# Transceivers_Ver2.net
KiCad netlist of a schematic drawn in EAGLE
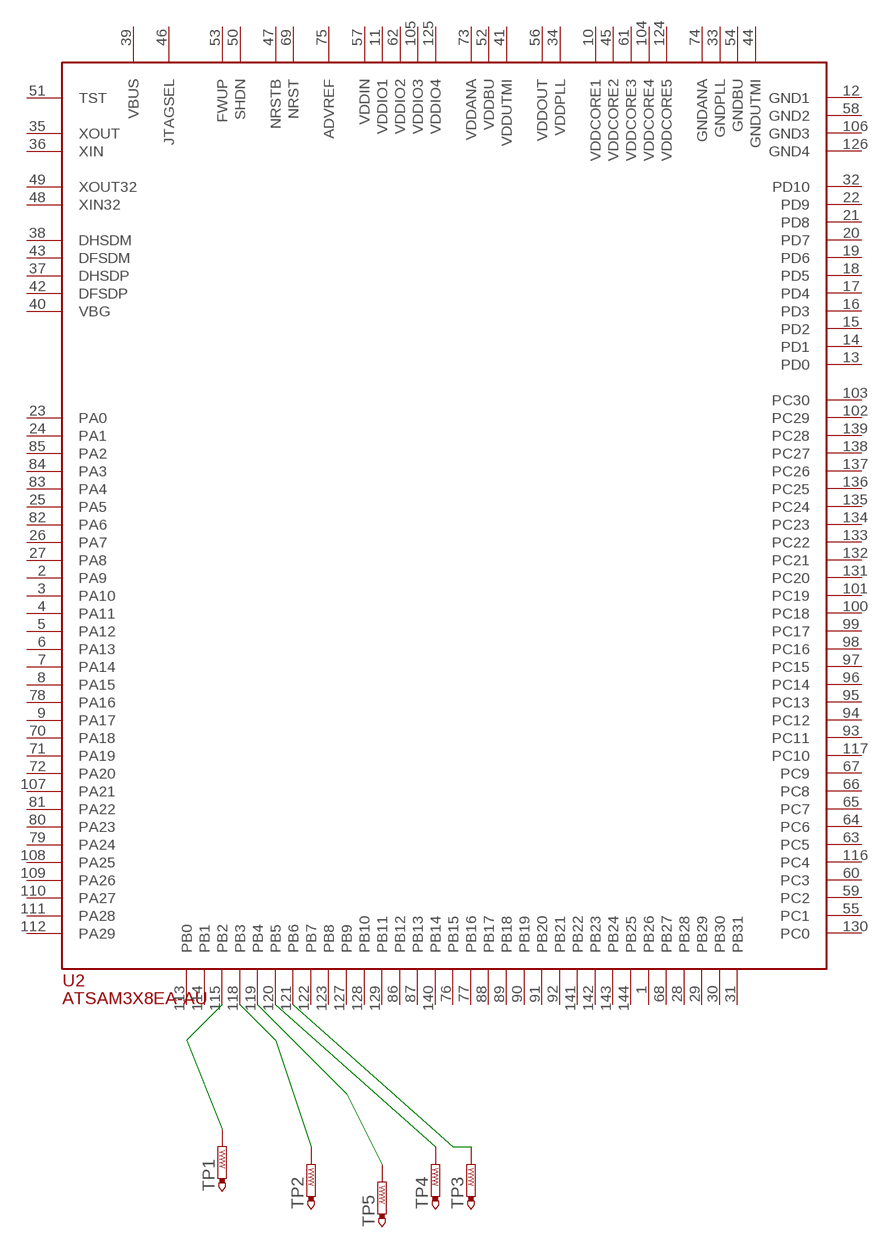
[diagram p0: schematic, sheet 1, part 1 of 2]
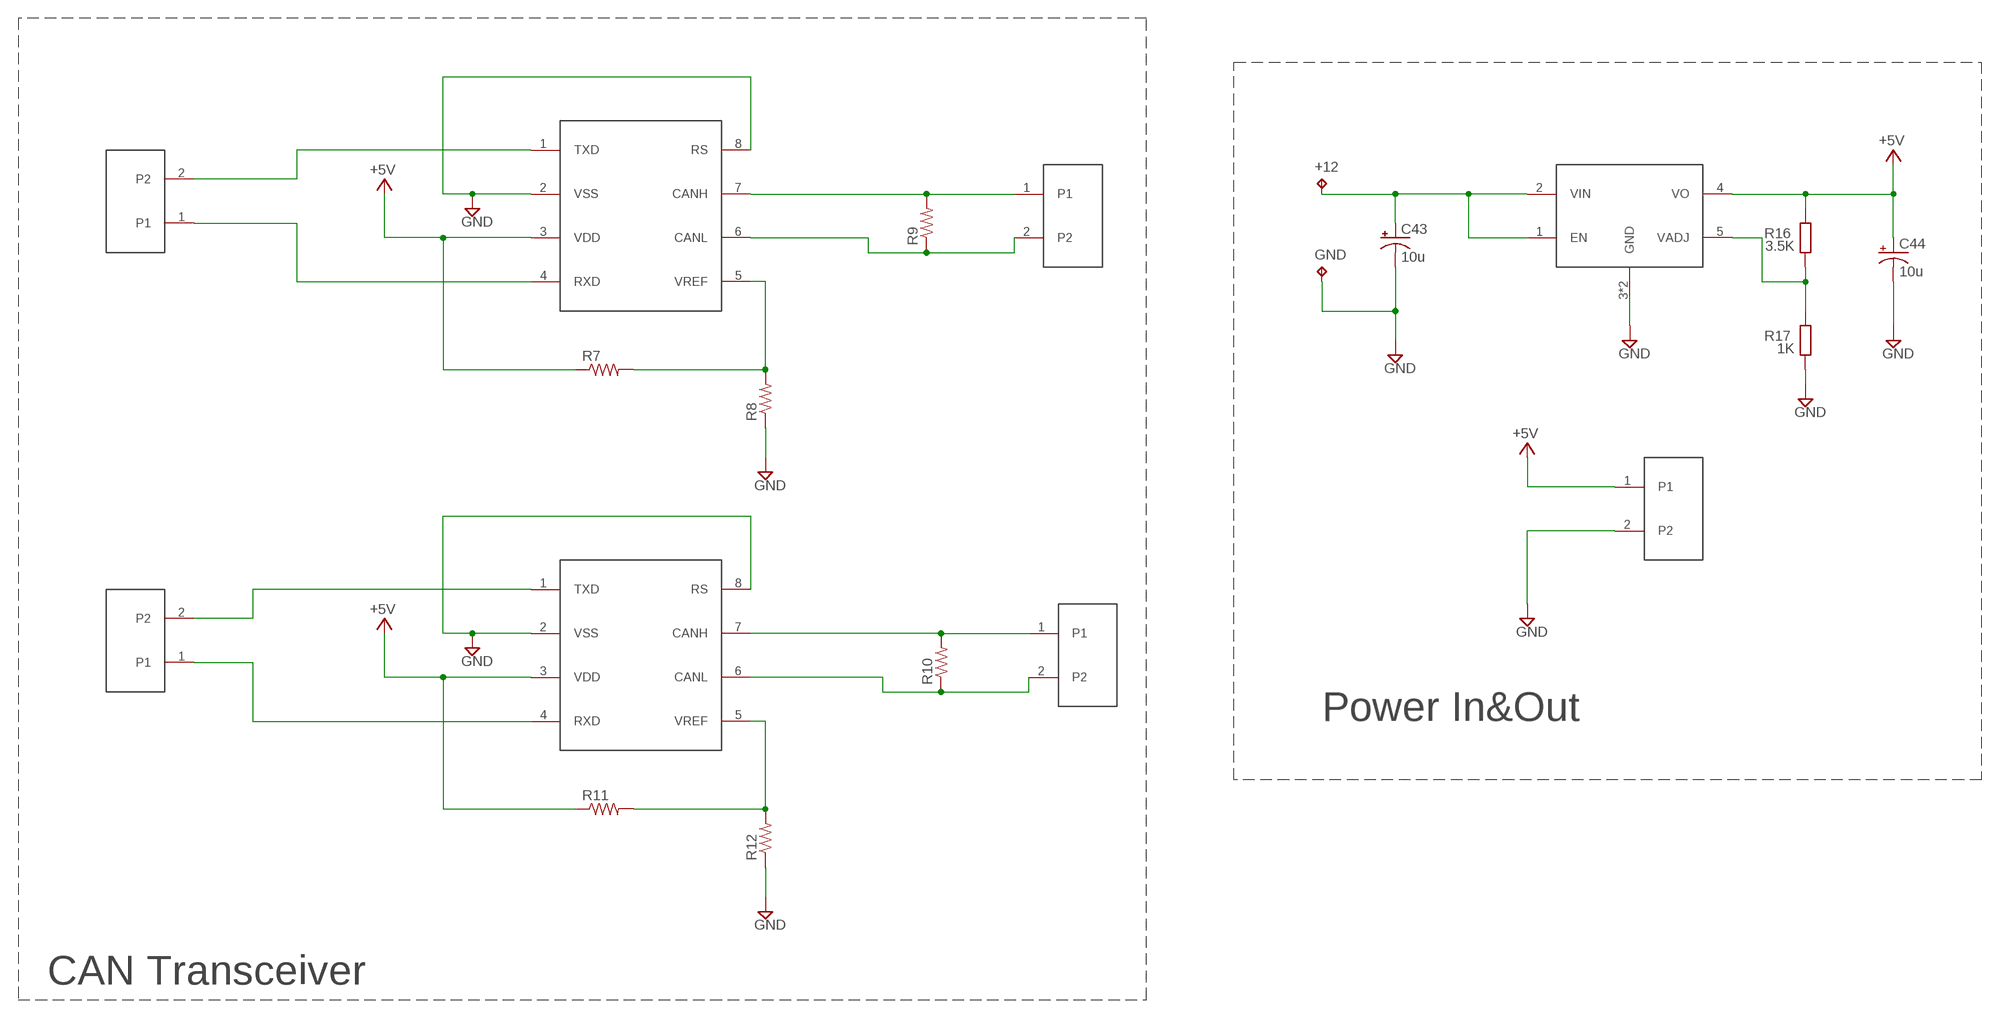
[diagram p1: schematic, sheet 1, part 2 of 2]

(export (version "E")
  (design (tool "Eeschema 10.0.6"))
  (components
    (comp (ref "+12")
      (value "TPPAD1-13")
      (footprint "eagle-import:P1-13")
      (libsource (lib "eagle-import") (part "TPPAD1-13"))
    )
    (comp (ref "C43")
      (value "10u")
      (footprint "eagle-import:153CLV-0405")
      (libsource (lib "eagle-import") (part "CPOL-US153CLV-0405"))
    )
    (comp (ref "C44")
      (value "10u")
      (footprint "eagle-import:153CLV-0405")
      (libsource (lib "eagle-import") (part "CPOL-US153CLV-0405"))
    )
    (comp (ref "CAN0")
      (value "CON-100MIL")
      (footprint "eagle-import:2X1-100MIL")
      (libsource (lib "eagle-import") (part "CON-100MIL"))
    )
    (comp (ref "CAN1")
      (value "CON-100MIL")
      (footprint "eagle-import:2X1-100MIL")
      (libsource (lib "eagle-import") (part "CON-100MIL"))
    )
    (comp (ref "GND")
      (value "TPPAD1-13")
      (footprint "eagle-import:P1-13")
      (libsource (lib "eagle-import") (part "TPPAD1-13"))
    )
    (comp (ref "POWER")
      (value "CON-100MIL")
      (footprint "eagle-import:2X1-100MIL")
      (libsource (lib "eagle-import") (part "CON-100MIL"))
    )
    (comp (ref "R7")
      (value "R-US_R0805")
      (footprint "eagle-import:R0805")
      (libsource (lib "eagle-import") (part "R-US_R0805"))
    )
    (comp (ref "R8")
      (value "R-US_R0805")
      (footprint "eagle-import:R0805")
      (libsource (lib "eagle-import") (part "R-US_R0805"))
    )
    (comp (ref "R9")
      (value "R-US_R0805")
      (footprint "eagle-import:R0805")
      (libsource (lib "eagle-import") (part "R-US_R0805"))
    )
    (comp (ref "R10")
      (value "R-US_R0805")
      (footprint "eagle-import:R0805")
      (libsource (lib "eagle-import") (part "R-US_R0805"))
    )
    (comp (ref "R11")
      (value "R-US_R0805")
      (footprint "eagle-import:R0805")
      (libsource (lib "eagle-import") (part "R-US_R0805"))
    )
    (comp (ref "R12")
      (value "R-US_R0805")
      (footprint "eagle-import:R0805")
      (libsource (lib "eagle-import") (part "R-US_R0805"))
    )
    (comp (ref "R16")
      (value "3.5K")
      (footprint "eagle-import:R0805")
      (libsource (lib "eagle-import") (part "R-EU_R0805"))
    )
    (comp (ref "R17")
      (value "1K")
      (footprint "eagle-import:R0805")
      (libsource (lib "eagle-import") (part "R-EU_R0805"))
    )
    (comp (ref "TP1")
      (value "PTR1PAD1-13Y")
      (footprint "eagle-import:P1-13Y")
      (libsource (lib "eagle-import") (part "PTR1PAD1-13Y"))
    )
    (comp (ref "TP2")
      (value "PTR1PAD1-13Y")
      (footprint "eagle-import:P1-13Y")
      (libsource (lib "eagle-import") (part "PTR1PAD1-13Y"))
    )
    (comp (ref "TP3")
      (value "PTR1PAD1-13Y")
      (footprint "eagle-import:P1-13Y")
      (libsource (lib "eagle-import") (part "PTR1PAD1-13Y"))
    )
    (comp (ref "TP4")
      (value "PTR1PAD1-13Y")
      (footprint "eagle-import:P1-13Y")
      (libsource (lib "eagle-import") (part "PTR1PAD1-13Y"))
    )
    (comp (ref "TP5")
      (value "PTR1PAD1-13Y")
      (footprint "eagle-import:P1-13Y")
      (libsource (lib "eagle-import") (part "PTR1PAD1-13Y"))
    )
    (comp (ref "TXRX0")
      (value "CON-100MIL")
      (footprint "eagle-import:2X1-100MIL")
      (libsource (lib "eagle-import") (part "CON-100MIL"))
    )
    (comp (ref "TXRX1")
      (value "CON-100MIL")
      (footprint "eagle-import:2X1-100MIL")
      (libsource (lib "eagle-import") (part "CON-100MIL"))
    )
    (comp (ref "U1")
      (value "MCP2551")
      (footprint "eagle-import:SOIC8")
      (libsource (lib "eagle-import") (part "MCP2551"))
    )
    (comp (ref "U2")
      (value "ATSAM3X8EA-AU")
      (footprint "eagle-import:LQFP144")
      (libsource (lib "eagle-import") (part "ATSAM3X/AAU"))
    )
    (comp (ref "U4")
      (value "MCP2551")
      (footprint "eagle-import:SOIC8")
      (libsource (lib "eagle-import") (part "MCP2551"))
    )
    (comp (ref "U5")
      (value "TLF1963TBATMA1")
      (footprint "eagle-import:DPAK")
      (libsource (lib "eagle-import") (part "TLF1963"))
    )
  )
  (nets
    (net (code "1") (name "+5V") (class "Default")
      (node (ref "C44") (pin "+") (pinfunction "+_+") (pintype "passive"))
      (node (ref "POWER") (pin "1") (pinfunction "P1_1") (pintype "bidirectional"))
      (node (ref "R11") (pin "1") (pinfunction "1_1") (pintype "passive"))
      (node (ref "R16") (pin "2") (pinfunction "2_2") (pintype "passive"))
      (node (ref "R7") (pin "1") (pinfunction "1_1") (pintype "passive"))
      (node (ref "U1") (pin "3") (pinfunction "VDD_3") (pintype "bidirectional"))
      (node (ref "U4") (pin "3") (pinfunction "VDD_3") (pintype "bidirectional"))
      (node (ref "U5") (pin "4") (pinfunction "VO_4") (pintype "bidirectional"))
    )
    (net (code "2") (name "/ADVREF") (class "Default")
      (node (ref "U2") (pin "75") (pinfunction "ADVREF_75") (pintype "power_in"))
    )
    (net (code "3") (name "/GND1") (class "Default")
      (node (ref "U2") (pin "12") (pinfunction "GND1_12") (pintype "power_in"))
    )
    (net (code "4") (name "/GND2") (class "Default")
      (node (ref "U2") (pin "58") (pinfunction "GND2_58") (pintype "power_in"))
    )
    (net (code "5") (name "/GND3") (class "Default")
      (node (ref "U2") (pin "106") (pinfunction "GND3_106") (pintype "power_in"))
    )
    (net (code "6") (name "/GND4") (class "Default")
      (node (ref "U2") (pin "126") (pinfunction "GND4_126") (pintype "power_in"))
    )
    (net (code "7") (name "/GNDANA") (class "Default")
      (node (ref "U2") (pin "74") (pinfunction "GNDANA_74") (pintype "power_in"))
    )
    (net (code "8") (name "/GNDBU") (class "Default")
      (node (ref "U2") (pin "54") (pinfunction "GNDBU_54") (pintype "power_in"))
    )
    (net (code "9") (name "/GNDPLL") (class "Default")
      (node (ref "U2") (pin "33") (pinfunction "GNDPLL_33") (pintype "power_in"))
    )
    (net (code "10") (name "/GNDUTMI") (class "Default")
      (node (ref "U2") (pin "44") (pinfunction "GNDUTMI_44") (pintype "power_in"))
    )
    (net (code "11") (name "/VBUS") (class "Default")
      (node (ref "U2") (pin "39") (pinfunction "VBUS_39") (pintype "power_in"))
    )
    (net (code "12") (name "/VDDANA") (class "Default")
      (node (ref "U2") (pin "73") (pinfunction "VDDANA_73") (pintype "power_in"))
    )
    (net (code "13") (name "/VDDBU") (class "Default")
      (node (ref "U2") (pin "52") (pinfunction "VDDBU_52") (pintype "power_in"))
    )
    (net (code "14") (name "/VDDIN") (class "Default")
      (node (ref "U2") (pin "57") (pinfunction "VDDIN_57") (pintype "power_in"))
    )
    (net (code "15") (name "/VDDIO1") (class "Default")
      (node (ref "U2") (pin "11") (pinfunction "VDDIO1_11") (pintype "power_in"))
    )
    (net (code "16") (name "/VDDIO2") (class "Default")
      (node (ref "U2") (pin "62") (pinfunction "VDDIO2_62") (pintype "power_in"))
    )
    (net (code "17") (name "/VDDIO3") (class "Default")
      (node (ref "U2") (pin "105") (pinfunction "VDDIO3_105") (pintype "power_in"))
    )
    (net (code "18") (name "/VDDIO4") (class "Default")
      (node (ref "U2") (pin "125") (pinfunction "VDDIO4_125") (pintype "power_in"))
    )
    (net (code "19") (name "GND") (class "Default")
      (node (ref "C43") (pin "-") (pinfunction "-_-") (pintype "passive"))
      (node (ref "C44") (pin "-") (pinfunction "-_-") (pintype "passive"))
      (node (ref "GND") (pin "TP") (pinfunction "TP_TP") (pintype "input"))
      (node (ref "POWER") (pin "2") (pinfunction "P2_2") (pintype "bidirectional"))
      (node (ref "R12") (pin "1") (pinfunction "1_1") (pintype "passive"))
      (node (ref "R17") (pin "1") (pinfunction "1_1") (pintype "passive"))
      (node (ref "R8") (pin "1") (pinfunction "1_1") (pintype "passive"))
      (node (ref "U1") (pin "2") (pinfunction "VSS_2") (pintype "bidirectional"))
      (node (ref "U1") (pin "8") (pinfunction "RS_8") (pintype "bidirectional"))
      (node (ref "U4") (pin "2") (pinfunction "VSS_2") (pintype "bidirectional"))
      (node (ref "U4") (pin "8") (pinfunction "RS_8") (pintype "bidirectional"))
      (node (ref "U5") (pin "3") (pinfunction "GND_3") (pintype "bidirectional"))
      (node (ref "U5") (pin "6") (pinfunction "GND_6") (pintype "bidirectional"))
    )
    (net (code "20") (name "Net-(CAN0-P1)") (class "Default")
      (node (ref "CAN0") (pin "1") (pinfunction "P1_1") (pintype "bidirectional"))
      (node (ref "R9") (pin "2") (pinfunction "2_2") (pintype "passive"))
      (node (ref "U1") (pin "7") (pinfunction "CANH_7") (pintype "bidirectional"))
    )
    (net (code "21") (name "Net-(CAN0-P2)") (class "Default")
      (node (ref "CAN0") (pin "2") (pinfunction "P2_2") (pintype "bidirectional"))
      (node (ref "R9") (pin "1") (pinfunction "1_1") (pintype "passive"))
      (node (ref "U1") (pin "6") (pinfunction "CANL_6") (pintype "bidirectional"))
    )
    (net (code "22") (name "Net-(CAN1-P1)") (class "Default")
      (node (ref "CAN1") (pin "1") (pinfunction "P1_1") (pintype "bidirectional"))
      (node (ref "R10") (pin "2") (pinfunction "2_2") (pintype "passive"))
      (node (ref "U4") (pin "7") (pinfunction "CANH_7") (pintype "bidirectional"))
    )
    (net (code "23") (name "Net-(CAN1-P2)") (class "Default")
      (node (ref "CAN1") (pin "2") (pinfunction "P2_2") (pintype "bidirectional"))
      (node (ref "R10") (pin "1") (pinfunction "1_1") (pintype "passive"))
      (node (ref "U4") (pin "6") (pinfunction "CANL_6") (pintype "bidirectional"))
    )
    (net (code "24") (name "Net-(TXRX0-P1)") (class "Default")
      (node (ref "TXRX0") (pin "1") (pinfunction "P1_1") (pintype "bidirectional"))
      (node (ref "U1") (pin "4") (pinfunction "RXD_4") (pintype "bidirectional"))
    )
    (net (code "25") (name "Net-(TXRX0-P2)") (class "Default")
      (node (ref "TXRX0") (pin "2") (pinfunction "P2_2") (pintype "bidirectional"))
      (node (ref "U1") (pin "1") (pinfunction "TXD_1") (pintype "bidirectional"))
    )
    (net (code "26") (name "Net-(TXRX1-P1)") (class "Default")
      (node (ref "TXRX1") (pin "1") (pinfunction "P1_1") (pintype "bidirectional"))
      (node (ref "U4") (pin "4") (pinfunction "RXD_4") (pintype "bidirectional"))
    )
    (net (code "27") (name "Net-(TXRX1-P2)") (class "Default")
      (node (ref "TXRX1") (pin "2") (pinfunction "P2_2") (pintype "bidirectional"))
      (node (ref "U4") (pin "1") (pinfunction "TXD_1") (pintype "bidirectional"))
    )
    (net (code "28") (name "Net-(U1-VREF)") (class "Default")
      (node (ref "R7") (pin "2") (pinfunction "2_2") (pintype "passive"))
      (node (ref "R8") (pin "2") (pinfunction "2_2") (pintype "passive"))
      (node (ref "U1") (pin "5") (pinfunction "VREF_5") (pintype "bidirectional"))
    )
    (net (code "29") (name "Net-(U2-PB2)") (class "Default")
      (node (ref "TP1") (pin "TP") (pinfunction "TP_TP") (pintype "input"))
      (node (ref "U2") (pin "115") (pinfunction "PB2_115") (pintype "bidirectional"))
    )
    (net (code "30") (name "Net-(U2-PB3)") (class "Default")
      (node (ref "TP2") (pin "TP") (pinfunction "TP_TP") (pintype "input"))
      (node (ref "U2") (pin "118") (pinfunction "PB3_118") (pintype "bidirectional"))
    )
    (net (code "31") (name "Net-(U2-PB4)") (class "Default")
      (node (ref "TP5") (pin "TP") (pinfunction "TP_TP") (pintype "input"))
      (node (ref "U2") (pin "119") (pinfunction "PB4_119") (pintype "bidirectional"))
    )
    (net (code "32") (name "Net-(U2-PB5)") (class "Default")
      (node (ref "TP4") (pin "TP") (pinfunction "TP_TP") (pintype "input"))
      (node (ref "U2") (pin "120") (pinfunction "PB5_120") (pintype "bidirectional"))
    )
    (net (code "33") (name "Net-(U2-PB6)") (class "Default")
      (node (ref "TP3") (pin "TP") (pinfunction "TP_TP") (pintype "input"))
      (node (ref "U2") (pin "121") (pinfunction "PB6_121") (pintype "bidirectional"))
    )
    (net (code "34") (name "Net-(U4-VREF)") (class "Default")
      (node (ref "R11") (pin "2") (pinfunction "2_2") (pintype "passive"))
      (node (ref "R12") (pin "2") (pinfunction "2_2") (pintype "passive"))
      (node (ref "U4") (pin "5") (pinfunction "VREF_5") (pintype "bidirectional"))
    )
    (net (code "35") (name "Net-(U5-EN)") (class "Default")
      (node (ref "+12") (pin "TP") (pinfunction "TP_TP") (pintype "input"))
      (node (ref "C43") (pin "+") (pinfunction "+_+") (pintype "passive"))
      (node (ref "U5") (pin "1") (pinfunction "EN_1") (pintype "bidirectional"))
      (node (ref "U5") (pin "2") (pinfunction "VIN_2") (pintype "bidirectional"))
    )
    (net (code "36") (name "Net-(U5-VADJ)") (class "Default")
      (node (ref "R16") (pin "1") (pinfunction "1_1") (pintype "passive"))
      (node (ref "R17") (pin "2") (pinfunction "2_2") (pintype "passive"))
      (node (ref "U5") (pin "5") (pinfunction "VADJ_5") (pintype "bidirectional"))
    )
    (net (code "37") (name "unconnected-(U2-DFSDM-Pad43)") (class "Default")
      (node (ref "U2") (pin "43") (pinfunction "DFSDM_43") (pintype "input"))
    )
    (net (code "38") (name "unconnected-(U2-DFSDP-Pad42)") (class "Default")
      (node (ref "U2") (pin "42") (pinfunction "DFSDP_42") (pintype "input"))
    )
    (net (code "39") (name "unconnected-(U2-DHSDM-Pad38)") (class "Default")
      (node (ref "U2") (pin "38") (pinfunction "DHSDM_38") (pintype "bidirectional"))
    )
    (net (code "40") (name "unconnected-(U2-DHSDP-Pad37)") (class "Default")
      (node (ref "U2") (pin "37") (pinfunction "DHSDP_37") (pintype "bidirectional"))
    )
    (net (code "41") (name "unconnected-(U2-FWUP-Pad53)") (class "Default")
      (node (ref "U2") (pin "53") (pinfunction "FWUP_53") (pintype "input"))
    )
    (net (code "42") (name "unconnected-(U2-JTAGSEL-Pad46)") (class "Default")
      (node (ref "U2") (pin "46") (pinfunction "JTAGSEL_46") (pintype "input"))
    )
    (net (code "43") (name "unconnected-(U2-NRST-Pad69)") (class "Default")
      (node (ref "U2") (pin "69") (pinfunction "NRST_69") (pintype "bidirectional"))
    )
    (net (code "44") (name "unconnected-(U2-NRSTB-Pad47)") (class "Default")
      (node (ref "U2") (pin "47") (pinfunction "NRSTB_47") (pintype "input"))
    )
    (net (code "45") (name "unconnected-(U2-PA0-Pad23)") (class "Default")
      (node (ref "U2") (pin "23") (pinfunction "PA0_23") (pintype "bidirectional"))
    )
    (net (code "46") (name "unconnected-(U2-PA1-Pad24)") (class "Default")
      (node (ref "U2") (pin "24") (pinfunction "PA1_24") (pintype "bidirectional"))
    )
    (net (code "47") (name "unconnected-(U2-PA2-Pad85)") (class "Default")
      (node (ref "U2") (pin "85") (pinfunction "PA2_85") (pintype "bidirectional"))
    )
    (net (code "48") (name "unconnected-(U2-PA3-Pad84)") (class "Default")
      (node (ref "U2") (pin "84") (pinfunction "PA3_84") (pintype "bidirectional"))
    )
    (net (code "49") (name "unconnected-(U2-PA4-Pad83)") (class "Default")
      (node (ref "U2") (pin "83") (pinfunction "PA4_83") (pintype "bidirectional"))
    )
    (net (code "50") (name "unconnected-(U2-PA5-Pad25)") (class "Default")
      (node (ref "U2") (pin "25") (pinfunction "PA5_25") (pintype "bidirectional"))
    )
    (net (code "51") (name "unconnected-(U2-PA6-Pad82)") (class "Default")
      (node (ref "U2") (pin "82") (pinfunction "PA6_82") (pintype "bidirectional"))
    )
    (net (code "52") (name "unconnected-(U2-PA7-Pad26)") (class "Default")
      (node (ref "U2") (pin "26") (pinfunction "PA7_26") (pintype "bidirectional"))
    )
    (net (code "53") (name "unconnected-(U2-PA8-Pad27)") (class "Default")
      (node (ref "U2") (pin "27") (pinfunction "PA8_27") (pintype "bidirectional"))
    )
    (net (code "54") (name "unconnected-(U2-PA9-Pad2)") (class "Default")
      (node (ref "U2") (pin "2") (pinfunction "PA9_2") (pintype "bidirectional"))
    )
    (net (code "55") (name "unconnected-(U2-PA10-Pad3)") (class "Default")
      (node (ref "U2") (pin "3") (pinfunction "PA10_3") (pintype "bidirectional"))
    )
    (net (code "56") (name "unconnected-(U2-PA11-Pad4)") (class "Default")
      (node (ref "U2") (pin "4") (pinfunction "PA11_4") (pintype "bidirectional"))
    )
    (net (code "57") (name "unconnected-(U2-PA12-Pad5)") (class "Default")
      (node (ref "U2") (pin "5") (pinfunction "PA12_5") (pintype "bidirectional"))
    )
    (net (code "58") (name "unconnected-(U2-PA13-Pad6)") (class "Default")
      (node (ref "U2") (pin "6") (pinfunction "PA13_6") (pintype "bidirectional"))
    )
    (net (code "59") (name "unconnected-(U2-PA14-Pad7)") (class "Default")
      (node (ref "U2") (pin "7") (pinfunction "PA14_7") (pintype "bidirectional"))
    )
    (net (code "60") (name "unconnected-(U2-PA15-Pad8)") (class "Default")
      (node (ref "U2") (pin "8") (pinfunction "PA15_8") (pintype "bidirectional"))
    )
    (net (code "61") (name "unconnected-(U2-PA16-Pad78)") (class "Default")
      (node (ref "U2") (pin "78") (pinfunction "PA16_78") (pintype "bidirectional"))
    )
    (net (code "62") (name "unconnected-(U2-PA17-Pad9)") (class "Default")
      (node (ref "U2") (pin "9") (pinfunction "PA17_9") (pintype "bidirectional"))
    )
    (net (code "63") (name "unconnected-(U2-PA18-Pad70)") (class "Default")
      (node (ref "U2") (pin "70") (pinfunction "PA18_70") (pintype "bidirectional"))
    )
    (net (code "64") (name "unconnected-(U2-PA19-Pad71)") (class "Default")
      (node (ref "U2") (pin "71") (pinfunction "PA19_71") (pintype "bidirectional"))
    )
    (net (code "65") (name "unconnected-(U2-PA20-Pad72)") (class "Default")
      (node (ref "U2") (pin "72") (pinfunction "PA20_72") (pintype "bidirectional"))
    )
    (net (code "66") (name "unconnected-(U2-PA21-Pad107)") (class "Default")
      (node (ref "U2") (pin "107") (pinfunction "PA21_107") (pintype "bidirectional"))
    )
    (net (code "67") (name "unconnected-(U2-PA22-Pad81)") (class "Default")
      (node (ref "U2") (pin "81") (pinfunction "PA22_81") (pintype "bidirectional"))
    )
    (net (code "68") (name "unconnected-(U2-PA23-Pad80)") (class "Default")
      (node (ref "U2") (pin "80") (pinfunction "PA23_80") (pintype "bidirectional"))
    )
    (net (code "69") (name "unconnected-(U2-PA24-Pad79)") (class "Default")
      (node (ref "U2") (pin "79") (pinfunction "PA24_79") (pintype "bidirectional"))
    )
    (net (code "70") (name "unconnected-(U2-PA25-Pad108)") (class "Default")
      (node (ref "U2") (pin "108") (pinfunction "PA25_108") (pintype "bidirectional"))
    )
    (net (code "71") (name "unconnected-(U2-PA26-Pad109)") (class "Default")
      (node (ref "U2") (pin "109") (pinfunction "PA26_109") (pintype "bidirectional"))
    )
    (net (code "72") (name "unconnected-(U2-PA27-Pad110)") (class "Default")
      (node (ref "U2") (pin "110") (pinfunction "PA27_110") (pintype "bidirectional"))
    )
    (net (code "73") (name "unconnected-(U2-PA28-Pad111)") (class "Default")
      (node (ref "U2") (pin "111") (pinfunction "PA28_111") (pintype "bidirectional"))
    )
    (net (code "74") (name "unconnected-(U2-PA29-Pad112)") (class "Default")
      (node (ref "U2") (pin "112") (pinfunction "PA29_112") (pintype "bidirectional"))
    )
    (net (code "75") (name "unconnected-(U2-PB0-Pad113)") (class "Default")
      (node (ref "U2") (pin "113") (pinfunction "PB0_113") (pintype "bidirectional"))
    )
    (net (code "76") (name "unconnected-(U2-PB1-Pad114)") (class "Default")
      (node (ref "U2") (pin "114") (pinfunction "PB1_114") (pintype "bidirectional"))
    )
    (net (code "77") (name "unconnected-(U2-PB7-Pad122)") (class "Default")
      (node (ref "U2") (pin "122") (pinfunction "PB7_122") (pintype "bidirectional"))
    )
    (net (code "78") (name "unconnected-(U2-PB8-Pad123)") (class "Default")
      (node (ref "U2") (pin "123") (pinfunction "PB8_123") (pintype "bidirectional"))
    )
    (net (code "79") (name "unconnected-(U2-PB9-Pad127)") (class "Default")
      (node (ref "U2") (pin "127") (pinfunction "PB9_127") (pintype "bidirectional"))
    )
    (net (code "80") (name "unconnected-(U2-PB10-Pad128)") (class "Default")
      (node (ref "U2") (pin "128") (pinfunction "PB10_128") (pintype "bidirectional"))
    )
    (net (code "81") (name "unconnected-(U2-PB11-Pad129)") (class "Default")
      (node (ref "U2") (pin "129") (pinfunction "PB11_129") (pintype "bidirectional"))
    )
    (net (code "82") (name "unconnected-(U2-PB12-Pad86)") (class "Default")
      (node (ref "U2") (pin "86") (pinfunction "PB12_86") (pintype "bidirectional"))
    )
    (net (code "83") (name "unconnected-(U2-PB13-Pad87)") (class "Default")
      (node (ref "U2") (pin "87") (pinfunction "PB13_87") (pintype "bidirectional"))
    )
    (net (code "84") (name "unconnected-(U2-PB14-Pad140)") (class "Default")
      (node (ref "U2") (pin "140") (pinfunction "PB14_140") (pintype "bidirectional"))
    )
    (net (code "85") (name "unconnected-(U2-PB15-Pad76)") (class "Default")
      (node (ref "U2") (pin "76") (pinfunction "PB15_76") (pintype "bidirectional"))
    )
    (net (code "86") (name "unconnected-(U2-PB16-Pad77)") (class "Default")
      (node (ref "U2") (pin "77") (pinfunction "PB16_77") (pintype "bidirectional"))
    )
    (net (code "87") (name "unconnected-(U2-PB17-Pad88)") (class "Default")
      (node (ref "U2") (pin "88") (pinfunction "PB17_88") (pintype "bidirectional"))
    )
    (net (code "88") (name "unconnected-(U2-PB18-Pad89)") (class "Default")
      (node (ref "U2") (pin "89") (pinfunction "PB18_89") (pintype "bidirectional"))
    )
    (net (code "89") (name "unconnected-(U2-PB19-Pad90)") (class "Default")
      (node (ref "U2") (pin "90") (pinfunction "PB19_90") (pintype "bidirectional"))
    )
    (net (code "90") (name "unconnected-(U2-PB20-Pad91)") (class "Default")
      (node (ref "U2") (pin "91") (pinfunction "PB20_91") (pintype "bidirectional"))
    )
    (net (code "91") (name "unconnected-(U2-PB21-Pad92)") (class "Default")
      (node (ref "U2") (pin "92") (pinfunction "PB21_92") (pintype "bidirectional"))
    )
    (net (code "92") (name "unconnected-(U2-PB22-Pad141)") (class "Default")
      (node (ref "U2") (pin "141") (pinfunction "PB22_141") (pintype "bidirectional"))
    )
    (net (code "93") (name "unconnected-(U2-PB23-Pad142)") (class "Default")
      (node (ref "U2") (pin "142") (pinfunction "PB23_142") (pintype "bidirectional"))
    )
    (net (code "94") (name "unconnected-(U2-PB24-Pad143)") (class "Default")
      (node (ref "U2") (pin "143") (pinfunction "PB24_143") (pintype "bidirectional"))
    )
    (net (code "95") (name "unconnected-(U2-PB25-Pad144)") (class "Default")
      (node (ref "U2") (pin "144") (pinfunction "PB25_144") (pintype "bidirectional"))
    )
    (net (code "96") (name "unconnected-(U2-PB26-Pad1)") (class "Default")
      (node (ref "U2") (pin "1") (pinfunction "PB26_1") (pintype "bidirectional"))
    )
    (net (code "97") (name "unconnected-(U2-PB27-Pad68)") (class "Default")
      (node (ref "U2") (pin "68") (pinfunction "PB27_68") (pintype "bidirectional"))
    )
    (net (code "98") (name "unconnected-(U2-PB28-Pad28)") (class "Default")
      (node (ref "U2") (pin "28") (pinfunction "PB28_28") (pintype "bidirectional"))
    )
    (net (code "99") (name "unconnected-(U2-PB29-Pad29)") (class "Default")
      (node (ref "U2") (pin "29") (pinfunction "PB29_29") (pintype "bidirectional"))
    )
    (net (code "100") (name "unconnected-(U2-PB30-Pad30)") (class "Default")
      (node (ref "U2") (pin "30") (pinfunction "PB30_30") (pintype "bidirectional"))
    )
    (net (code "101") (name "unconnected-(U2-PB31-Pad31)") (class "Default")
      (node (ref "U2") (pin "31") (pinfunction "PB31_31") (pintype "bidirectional"))
    )
    (net (code "102") (name "unconnected-(U2-PC0-Pad130)") (class "Default")
      (node (ref "U2") (pin "130") (pinfunction "PC0_130") (pintype "bidirectional"))
    )
    (net (code "103") (name "unconnected-(U2-PC1-Pad55)") (class "Default")
      (node (ref "U2") (pin "55") (pinfunction "PC1_55") (pintype "bidirectional"))
    )
    (net (code "104") (name "unconnected-(U2-PC2-Pad59)") (class "Default")
      (node (ref "U2") (pin "59") (pinfunction "PC2_59") (pintype "bidirectional"))
    )
    (net (code "105") (name "unconnected-(U2-PC3-Pad60)") (class "Default")
      (node (ref "U2") (pin "60") (pinfunction "PC3_60") (pintype "bidirectional"))
    )
    (net (code "106") (name "unconnected-(U2-PC4-Pad116)") (class "Default")
      (node (ref "U2") (pin "116") (pinfunction "PC4_116") (pintype "bidirectional"))
    )
    (net (code "107") (name "unconnected-(U2-PC5-Pad63)") (class "Default")
      (node (ref "U2") (pin "63") (pinfunction "PC5_63") (pintype "bidirectional"))
    )
    (net (code "108") (name "unconnected-(U2-PC6-Pad64)") (class "Default")
      (node (ref "U2") (pin "64") (pinfunction "PC6_64") (pintype "bidirectional"))
    )
    (net (code "109") (name "unconnected-(U2-PC7-Pad65)") (class "Default")
      (node (ref "U2") (pin "65") (pinfunction "PC7_65") (pintype "bidirectional"))
    )
    (net (code "110") (name "unconnected-(U2-PC8-Pad66)") (class "Default")
      (node (ref "U2") (pin "66") (pinfunction "PC8_66") (pintype "bidirectional"))
    )
    (net (code "111") (name "unconnected-(U2-PC9-Pad67)") (class "Default")
      (node (ref "U2") (pin "67") (pinfunction "PC9_67") (pintype "bidirectional"))
    )
    (net (code "112") (name "unconnected-(U2-PC10-Pad117)") (class "Default")
      (node (ref "U2") (pin "117") (pinfunction "PC10_117") (pintype "bidirectional"))
    )
    (net (code "113") (name "unconnected-(U2-PC11-Pad93)") (class "Default")
      (node (ref "U2") (pin "93") (pinfunction "PC11_93") (pintype "bidirectional"))
    )
    (net (code "114") (name "unconnected-(U2-PC12-Pad94)") (class "Default")
      (node (ref "U2") (pin "94") (pinfunction "PC12_94") (pintype "bidirectional"))
    )
    (net (code "115") (name "unconnected-(U2-PC13-Pad95)") (class "Default")
      (node (ref "U2") (pin "95") (pinfunction "PC13_95") (pintype "bidirectional"))
    )
    (net (code "116") (name "unconnected-(U2-PC14-Pad96)") (class "Default")
      (node (ref "U2") (pin "96") (pinfunction "PC14_96") (pintype "bidirectional"))
    )
    (net (code "117") (name "unconnected-(U2-PC15-Pad97)") (class "Default")
      (node (ref "U2") (pin "97") (pinfunction "PC15_97") (pintype "bidirectional"))
    )
    (net (code "118") (name "unconnected-(U2-PC16-Pad98)") (class "Default")
      (node (ref "U2") (pin "98") (pinfunction "PC16_98") (pintype "bidirectional"))
    )
    (net (code "119") (name "unconnected-(U2-PC17-Pad99)") (class "Default")
      (node (ref "U2") (pin "99") (pinfunction "PC17_99") (pintype "bidirectional"))
    )
    (net (code "120") (name "unconnected-(U2-PC18-Pad100)") (class "Default")
      (node (ref "U2") (pin "100") (pinfunction "PC18_100") (pintype "bidirectional"))
    )
    (net (code "121") (name "unconnected-(U2-PC19-Pad101)") (class "Default")
      (node (ref "U2") (pin "101") (pinfunction "PC19_101") (pintype "bidirectional"))
    )
    (net (code "122") (name "unconnected-(U2-PC20-Pad131)") (class "Default")
      (node (ref "U2") (pin "131") (pinfunction "PC20_131") (pintype "bidirectional"))
    )
    (net (code "123") (name "unconnected-(U2-PC21-Pad132)") (class "Default")
      (node (ref "U2") (pin "132") (pinfunction "PC21_132") (pintype "bidirectional"))
    )
    (net (code "124") (name "unconnected-(U2-PC22-Pad133)") (class "Default")
      (node (ref "U2") (pin "133") (pinfunction "PC22_133") (pintype "bidirectional"))
    )
    (net (code "125") (name "unconnected-(U2-PC23-Pad134)") (class "Default")
      (node (ref "U2") (pin "134") (pinfunction "PC23_134") (pintype "bidirectional"))
    )
    (net (code "126") (name "unconnected-(U2-PC24-Pad135)") (class "Default")
      (node (ref "U2") (pin "135") (pinfunction "PC24_135") (pintype "bidirectional"))
    )
    (net (code "127") (name "unconnected-(U2-PC25-Pad136)") (class "Default")
      (node (ref "U2") (pin "136") (pinfunction "PC25_136") (pintype "bidirectional"))
    )
    (net (code "128") (name "unconnected-(U2-PC26-Pad137)") (class "Default")
      (node (ref "U2") (pin "137") (pinfunction "PC26_137") (pintype "bidirectional"))
    )
    (net (code "129") (name "unconnected-(U2-PC27-Pad138)") (class "Default")
      (node (ref "U2") (pin "138") (pinfunction "PC27_138") (pintype "bidirectional"))
    )
    (net (code "130") (name "unconnected-(U2-PC28-Pad139)") (class "Default")
      (node (ref "U2") (pin "139") (pinfunction "PC28_139") (pintype "bidirectional"))
    )
    (net (code "131") (name "unconnected-(U2-PC29-Pad102)") (class "Default")
      (node (ref "U2") (pin "102") (pinfunction "PC29_102") (pintype "bidirectional"))
    )
    (net (code "132") (name "unconnected-(U2-PC30-Pad103)") (class "Default")
      (node (ref "U2") (pin "103") (pinfunction "PC30_103") (pintype "bidirectional"))
    )
    (net (code "133") (name "unconnected-(U2-PD0-Pad13)") (class "Default")
      (node (ref "U2") (pin "13") (pinfunction "PD0_13") (pintype "bidirectional"))
    )
    (net (code "134") (name "unconnected-(U2-PD1-Pad14)") (class "Default")
      (node (ref "U2") (pin "14") (pinfunction "PD1_14") (pintype "bidirectional"))
    )
    (net (code "135") (name "unconnected-(U2-PD2-Pad15)") (class "Default")
      (node (ref "U2") (pin "15") (pinfunction "PD2_15") (pintype "bidirectional"))
    )
    (net (code "136") (name "unconnected-(U2-PD3-Pad16)") (class "Default")
      (node (ref "U2") (pin "16") (pinfunction "PD3_16") (pintype "bidirectional"))
    )
    (net (code "137") (name "unconnected-(U2-PD4-Pad17)") (class "Default")
      (node (ref "U2") (pin "17") (pinfunction "PD4_17") (pintype "bidirectional"))
    )
    (net (code "138") (name "unconnected-(U2-PD5-Pad18)") (class "Default")
      (node (ref "U2") (pin "18") (pinfunction "PD5_18") (pintype "bidirectional"))
    )
    (net (code "139") (name "unconnected-(U2-PD6-Pad19)") (class "Default")
      (node (ref "U2") (pin "19") (pinfunction "PD6_19") (pintype "bidirectional"))
    )
    (net (code "140") (name "unconnected-(U2-PD7-Pad20)") (class "Default")
      (node (ref "U2") (pin "20") (pinfunction "PD7_20") (pintype "bidirectional"))
    )
    (net (code "141") (name "unconnected-(U2-PD8-Pad21)") (class "Default")
      (node (ref "U2") (pin "21") (pinfunction "PD8_21") (pintype "bidirectional"))
    )
    (net (code "142") (name "unconnected-(U2-PD9-Pad22)") (class "Default")
      (node (ref "U2") (pin "22") (pinfunction "PD9_22") (pintype "bidirectional"))
    )
    (net (code "143") (name "unconnected-(U2-PD10-Pad32)") (class "Default")
      (node (ref "U2") (pin "32") (pinfunction "PD10_32") (pintype "bidirectional"))
    )
    (net (code "144") (name "unconnected-(U2-SHDN-Pad50)") (class "Default")
      (node (ref "U2") (pin "50") (pinfunction "SHDN_50") (pintype "output"))
    )
    (net (code "145") (name "unconnected-(U2-TST-Pad51)") (class "Default")
      (node (ref "U2") (pin "51") (pinfunction "TST_51") (pintype "input"))
    )
    (net (code "146") (name "unconnected-(U2-VBG-Pad40)") (class "Default")
      (node (ref "U2") (pin "40") (pinfunction "VBG_40") (pintype "passive"))
    )
    (net (code "147") (name "unconnected-(U2-VDDCORE1-Pad10)") (class "Default")
      (node (ref "U2") (pin "10") (pinfunction "VDDCORE1_10") (pintype "input"))
    )
    (net (code "148") (name "unconnected-(U2-VDDCORE2-Pad45)") (class "Default")
      (node (ref "U2") (pin "45") (pinfunction "VDDCORE2_45") (pintype "input"))
    )
    (net (code "149") (name "unconnected-(U2-VDDCORE3-Pad61)") (class "Default")
      (node (ref "U2") (pin "61") (pinfunction "VDDCORE3_61") (pintype "input"))
    )
    (net (code "150") (name "unconnected-(U2-VDDCORE4-Pad104)") (class "Default")
      (node (ref "U2") (pin "104") (pinfunction "VDDCORE4_104") (pintype "input"))
    )
    (net (code "151") (name "unconnected-(U2-VDDCORE5-Pad124)") (class "Default")
      (node (ref "U2") (pin "124") (pinfunction "VDDCORE5_124") (pintype "input"))
    )
    (net (code "152") (name "unconnected-(U2-VDDOUT-Pad56)") (class "Default")
      (node (ref "U2") (pin "56") (pinfunction "VDDOUT_56") (pintype "output"))
    )
    (net (code "153") (name "unconnected-(U2-VDDPLL-Pad34)") (class "Default")
      (node (ref "U2") (pin "34") (pinfunction "VDDPLL_34") (pintype "input"))
    )
    (net (code "154") (name "unconnected-(U2-VDDUTMI-Pad41)") (class "Default")
      (node (ref "U2") (pin "41") (pinfunction "VDDUTMI_41") (pintype "input"))
    )
    (net (code "155") (name "unconnected-(U2-XIN-Pad36)") (class "Default")
      (node (ref "U2") (pin "36") (pinfunction "XIN_36") (pintype "input"))
    )
    (net (code "156") (name "unconnected-(U2-XIN32-Pad48)") (class "Default")
      (node (ref "U2") (pin "48") (pinfunction "XIN32_48") (pintype "output"))
    )
    (net (code "157") (name "unconnected-(U2-XOUT-Pad35)") (class "Default")
      (node (ref "U2") (pin "35") (pinfunction "XOUT_35") (pintype "output"))
    )
    (net (code "158") (name "unconnected-(U2-XOUT32-Pad49)") (class "Default")
      (node (ref "U2") (pin "49") (pinfunction "XOUT32_49") (pintype "output"))
    )
  )
)
